# tophat.net
KiCad netlist of a schematic drawn in EAGLE
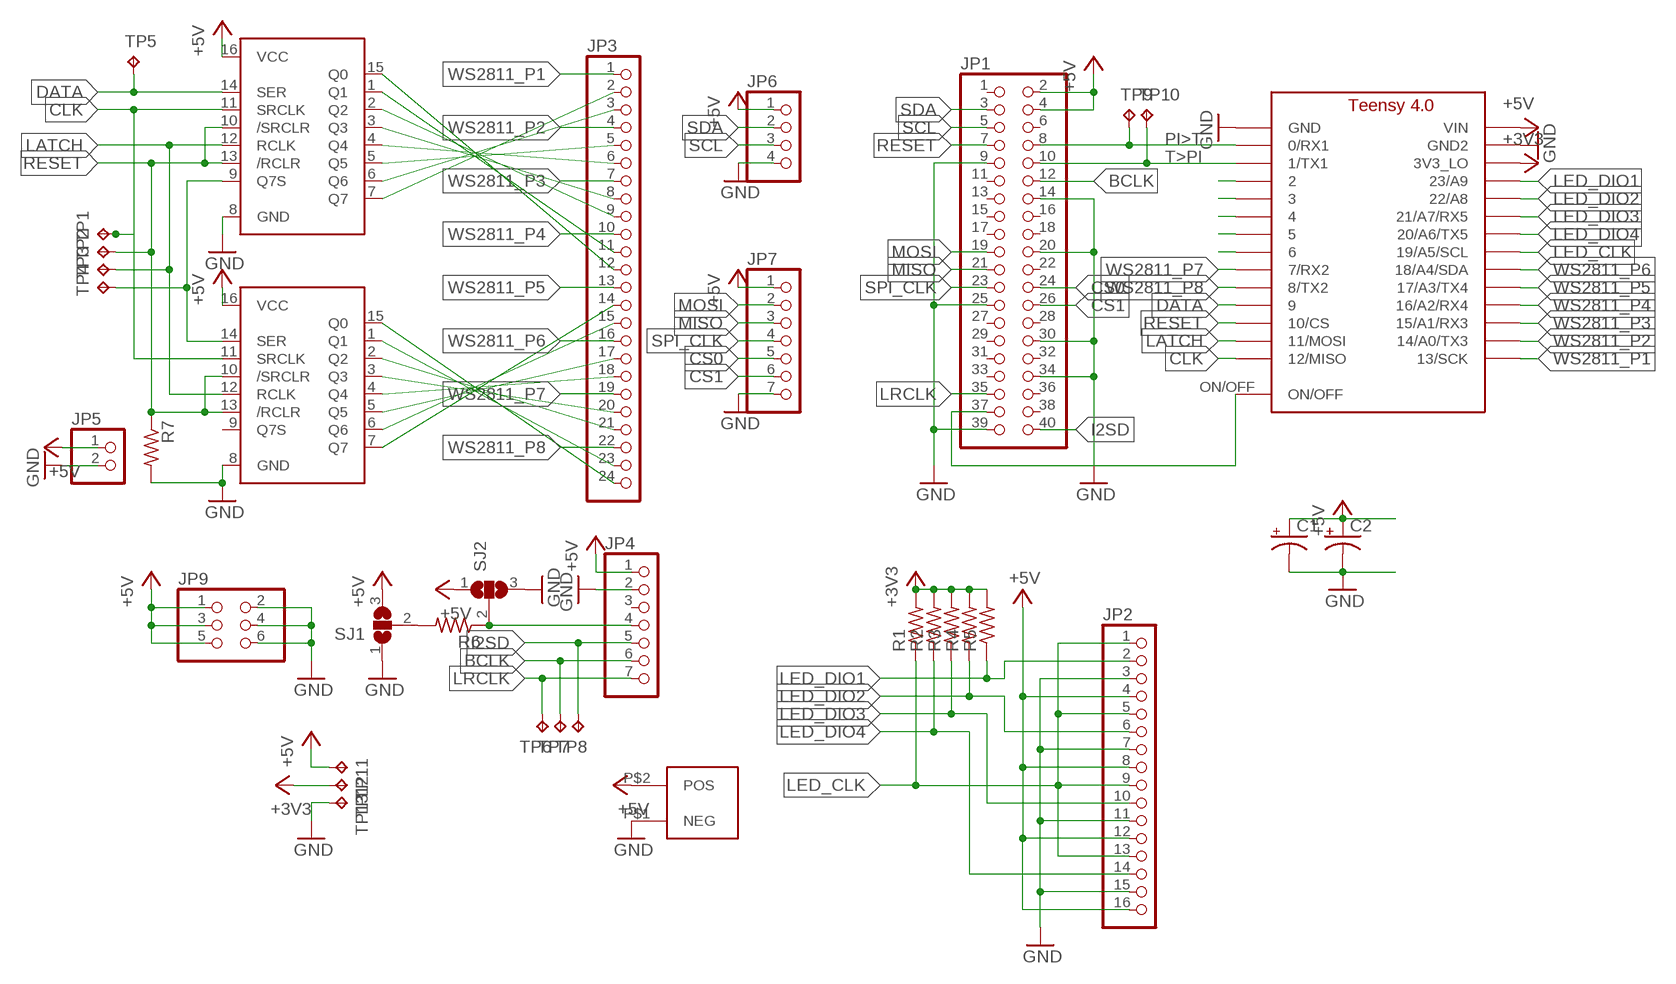
[diagram p0: schematic, sheet 1]

(export (version "E")
  (design (tool "Eeschema 10.0.6"))
  (components
    (comp (ref "C1")
      (value "CPOL-USE5-10.5")
      (footprint "eagle-import:E5-10,5")
      (libsource (lib "eagle-import") (part "CPOL-USE5-10.5"))
    )
    (comp (ref "C2")
      (value "CPOL-USE5-10.5")
      (footprint "eagle-import:E5-10,5")
      (libsource (lib "eagle-import") (part "CPOL-USE5-10.5"))
    )
    (comp (ref "JP1")
      (value "PINHD-2X20")
      (footprint "eagle-import:2X20")
      (libsource (lib "eagle-import") (part "PINHD-2X20"))
    )
    (comp (ref "JP2")
      (value "PINHD-1X16/90")
      (footprint "eagle-import:1X16_90")
      (libsource (lib "eagle-import") (part "PINHD-1X16/90"))
    )
    (comp (ref "JP3")
      (value "PINHD-1X24/90")
      (footprint "eagle-import:1X24_90")
      (libsource (lib "eagle-import") (part "PINHD-1X24/90"))
    )
    (comp (ref "JP4")
      (value "PINHD-1X7")
      (footprint "eagle-import:1X07")
      (libsource (lib "eagle-import") (part "PINHD-1X7"))
    )
    (comp (ref "JP5")
      (value "PINHD-1X2")
      (footprint "eagle-import:1X02")
      (libsource (lib "eagle-import") (part "PINHD-1X2"))
    )
    (comp (ref "JP6")
      (value "PINHD-1X4")
      (footprint "eagle-import:1X04")
      (libsource (lib "eagle-import") (part "PINHD-1X4"))
    )
    (comp (ref "JP7")
      (value "PINHD-1X7")
      (footprint "eagle-import:1X07")
      (libsource (lib "eagle-import") (part "PINHD-1X7"))
    )
    (comp (ref "JP8")
      (value "PWR_CONN")
      (footprint "eagle-import:PWR_CONN")
      (libsource (lib "eagle-import") (part "PWR_CONN"))
    )
    (comp (ref "JP9")
      (value "PINHD-2X3")
      (footprint "eagle-import:2X03")
      (libsource (lib "eagle-import") (part "PINHD-2X3"))
    )
    (comp (ref "R1")
      (value "R-US_0207/10")
      (footprint "eagle-import:0207_10")
      (libsource (lib "eagle-import") (part "R-US_0207/10"))
    )
    (comp (ref "R2")
      (value "R-US_0207/10")
      (footprint "eagle-import:0207_10")
      (libsource (lib "eagle-import") (part "R-US_0207/10"))
    )
    (comp (ref "R3")
      (value "R-US_0207/10")
      (footprint "eagle-import:0207_10")
      (libsource (lib "eagle-import") (part "R-US_0207/10"))
    )
    (comp (ref "R4")
      (value "R-US_0207/10")
      (footprint "eagle-import:0207_10")
      (libsource (lib "eagle-import") (part "R-US_0207/10"))
    )
    (comp (ref "R5")
      (value "R-US_0207/10")
      (footprint "eagle-import:0207_10")
      (libsource (lib "eagle-import") (part "R-US_0207/10"))
    )
    (comp (ref "R6")
      (value "R-US_0207/10")
      (footprint "eagle-import:0207_10")
      (libsource (lib "eagle-import") (part "R-US_0207/10"))
    )
    (comp (ref "R7")
      (value "R-US_0207/10")
      (footprint "eagle-import:0207_10")
      (libsource (lib "eagle-import") (part "R-US_0207/10"))
    )
    (comp (ref "SJ1")
      (value "SJ2W")
      (footprint "eagle-import:SJ_2")
      (libsource (lib "eagle-import") (part "SJ2W"))
    )
    (comp (ref "SJ2")
      (value "SJ2W")
      (footprint "eagle-import:SJ_2")
      (libsource (lib "eagle-import") (part "SJ2W"))
    )
    (comp (ref "TP1")
      (value "TPB2,54")
      (footprint "eagle-import:B2,54")
      (libsource (lib "eagle-import") (part "TPB2,54"))
    )
    (comp (ref "TP2")
      (value "TPB2,54")
      (footprint "eagle-import:B2,54")
      (libsource (lib "eagle-import") (part "TPB2,54"))
    )
    (comp (ref "TP3")
      (value "TPB2,54")
      (footprint "eagle-import:B2,54")
      (libsource (lib "eagle-import") (part "TPB2,54"))
    )
    (comp (ref "TP4")
      (value "TPB2,54")
      (footprint "eagle-import:B2,54")
      (libsource (lib "eagle-import") (part "TPB2,54"))
    )
    (comp (ref "TP5")
      (value "TPB2,54")
      (footprint "eagle-import:B2,54")
      (libsource (lib "eagle-import") (part "TPB2,54"))
    )
    (comp (ref "TP6")
      (value "TPB2,54")
      (footprint "eagle-import:B2,54")
      (libsource (lib "eagle-import") (part "TPB2,54"))
    )
    (comp (ref "TP7")
      (value "TPB2,54")
      (footprint "eagle-import:B2,54")
      (libsource (lib "eagle-import") (part "TPB2,54"))
    )
    (comp (ref "TP8")
      (value "TPB2,54")
      (footprint "eagle-import:B2,54")
      (libsource (lib "eagle-import") (part "TPB2,54"))
    )
    (comp (ref "TP9")
      (value "TPB2,54")
      (footprint "eagle-import:B2,54")
      (libsource (lib "eagle-import") (part "TPB2,54"))
    )
    (comp (ref "TP10")
      (value "TPB2,54")
      (footprint "eagle-import:B2,54")
      (libsource (lib "eagle-import") (part "TPB2,54"))
    )
    (comp (ref "TP11")
      (value "TPB2,54")
      (footprint "eagle-import:B2,54")
      (libsource (lib "eagle-import") (part "TPB2,54"))
    )
    (comp (ref "TP12")
      (value "TPB2,54")
      (footprint "eagle-import:B2,54")
      (libsource (lib "eagle-import") (part "TPB2,54"))
    )
    (comp (ref "TP13")
      (value "TPB2,54")
      (footprint "eagle-import:B2,54")
      (libsource (lib "eagle-import") (part "TPB2,54"))
    )
    (comp (ref "U$1")
      (value "TEENSY_4.0")
      (footprint "eagle-import:TEENSY_4.0")
      (libsource (lib "eagle-import") (part "TEENSY_4.0"))
    )
    (comp (ref "U$2")
      (value "74AHCT95")
      (footprint "eagle-import:SOIC127P600X175-16N")
      (libsource (lib "eagle-import") (part "74AHCT95"))
    )
    (comp (ref "U$3")
      (value "74AHCT95")
      (footprint "eagle-import:SOIC127P600X175-16N")
      (libsource (lib "eagle-import") (part "74AHCT95"))
    )
  )
  (nets
    (net (code "1") (name "+3V3") (class "Default")
      (node (ref "R1") (pin "2") (pinfunction "2_2") (pintype "passive"))
      (node (ref "R2") (pin "2") (pinfunction "2_2") (pintype "passive"))
      (node (ref "R3") (pin "2") (pinfunction "2_2") (pintype "passive"))
      (node (ref "R4") (pin "2") (pinfunction "2_2") (pintype "passive"))
      (node (ref "R5") (pin "2") (pinfunction "2_2") (pintype "passive"))
      (node (ref "TP12") (pin "TP") (pinfunction "TP_TP") (pintype "input"))
      (node (ref "U$1") (pin "3V3_LO") (pinfunction "3V3_LO_3V3_LO") (pintype "bidirectional"))
    )
    (net (code "2") (name "+5V") (class "Default")
      (node (ref "C1") (pin "+") (pinfunction "+_+") (pintype "passive"))
      (node (ref "C2") (pin "+") (pinfunction "+_+") (pintype "passive"))
      (node (ref "JP1") (pin "2") (pinfunction "2_2") (pintype "passive"))
      (node (ref "JP1") (pin "4") (pinfunction "4_4") (pintype "passive"))
      (node (ref "JP2") (pin "12") (pinfunction "12_12") (pintype "passive"))
      (node (ref "JP2") (pin "16") (pinfunction "16_16") (pintype "passive"))
      (node (ref "JP2") (pin "4") (pinfunction "4_4") (pintype "passive"))
      (node (ref "JP2") (pin "8") (pinfunction "8_8") (pintype "passive"))
      (node (ref "JP4") (pin "1") (pinfunction "1_1") (pintype "passive"))
      (node (ref "JP5") (pin "1") (pinfunction "1_1") (pintype "passive"))
      (node (ref "JP6") (pin "1") (pinfunction "1_1") (pintype "passive"))
      (node (ref "JP7") (pin "1") (pinfunction "1_1") (pintype "passive"))
      (node (ref "JP8") (pin "P$2") (pinfunction "POS_P$2") (pintype "bidirectional"))
      (node (ref "JP9") (pin "1") (pinfunction "1_1") (pintype "passive"))
      (node (ref "JP9") (pin "3") (pinfunction "3_3") (pintype "passive"))
      (node (ref "JP9") (pin "5") (pinfunction "5_5") (pintype "passive"))
      (node (ref "SJ1") (pin "3") (pinfunction "3_3") (pintype "passive"))
      (node (ref "SJ2") (pin "1") (pinfunction "1_1") (pintype "passive"))
      (node (ref "TP11") (pin "TP") (pinfunction "TP_TP") (pintype "input"))
      (node (ref "U$1") (pin "VIN") (pinfunction "VIN_VIN") (pintype "bidirectional"))
      (node (ref "U$2") (pin "16") (pinfunction "VCC_16") (pintype "bidirectional"))
      (node (ref "U$3") (pin "16") (pinfunction "VCC_16") (pintype "bidirectional"))
    )
    (net (code "3") (name "/PI>T") (class "Default")
      (node (ref "JP1") (pin "8") (pinfunction "8_8") (pintype "passive"))
      (node (ref "TP9") (pin "TP") (pinfunction "TP_TP") (pintype "input"))
      (node (ref "U$1") (pin "0/RX") (pinfunction "0/RX1_0/RX") (pintype "bidirectional"))
    )
    (net (code "4") (name "/T>PI") (class "Default")
      (node (ref "JP1") (pin "10") (pinfunction "10_10") (pintype "passive"))
      (node (ref "TP10") (pin "TP") (pinfunction "TP_TP") (pintype "input"))
      (node (ref "U$1") (pin "1/TX") (pinfunction "1/TX1_1/TX") (pintype "bidirectional"))
    )
    (net (code "5") (name "BCLK") (class "Default")
      (node (ref "JP1") (pin "12") (pinfunction "12_12") (pintype "passive"))
      (node (ref "JP4") (pin "6") (pinfunction "6_6") (pintype "passive"))
      (node (ref "TP7") (pin "TP") (pinfunction "TP_TP") (pintype "input"))
    )
    (net (code "6") (name "CLK") (class "Default")
      (node (ref "TP1") (pin "TP") (pinfunction "TP_TP") (pintype "input"))
      (node (ref "U$1") (pin "12/MISO") (pinfunction "12/MISO_12/MISO") (pintype "bidirectional"))
      (node (ref "U$2") (pin "11") (pinfunction "SRCLK_11") (pintype "bidirectional"))
      (node (ref "U$3") (pin "11") (pinfunction "SRCLK_11") (pintype "bidirectional"))
    )
    (net (code "7") (name "CS0") (class "Default")
      (node (ref "JP1") (pin "24") (pinfunction "24_24") (pintype "passive"))
      (node (ref "JP7") (pin "5") (pinfunction "5_5") (pintype "passive"))
    )
    (net (code "8") (name "CS1") (class "Default")
      (node (ref "JP1") (pin "26") (pinfunction "26_26") (pintype "passive"))
      (node (ref "JP7") (pin "6") (pinfunction "6_6") (pintype "passive"))
    )
    (net (code "9") (name "DATA") (class "Default")
      (node (ref "TP5") (pin "TP") (pinfunction "TP_TP") (pintype "input"))
      (node (ref "U$1") (pin "9/CS") (pinfunction "9_9/CS") (pintype "bidirectional"))
      (node (ref "U$2") (pin "14") (pinfunction "SER_14") (pintype "bidirectional"))
    )
    (net (code "10") (name "GND") (class "Default")
      (node (ref "C1") (pin "-") (pinfunction "-_-") (pintype "passive"))
      (node (ref "C2") (pin "-") (pinfunction "-_-") (pintype "passive"))
      (node (ref "JP1") (pin "14") (pinfunction "14_14") (pintype "passive"))
      (node (ref "JP1") (pin "20") (pinfunction "20_20") (pintype "passive"))
      (node (ref "JP1") (pin "25") (pinfunction "25_25") (pintype "passive"))
      (node (ref "JP1") (pin "30") (pinfunction "30_30") (pintype "passive"))
      (node (ref "JP1") (pin "34") (pinfunction "34_34") (pintype "passive"))
      (node (ref "JP1") (pin "39") (pinfunction "39_39") (pintype "passive"))
      (node (ref "JP1") (pin "9") (pinfunction "9_9") (pintype "passive"))
      (node (ref "JP2") (pin "11") (pinfunction "11_11") (pintype "passive"))
      (node (ref "JP2") (pin "15") (pinfunction "15_15") (pintype "passive"))
      (node (ref "JP2") (pin "3") (pinfunction "3_3") (pintype "passive"))
      (node (ref "JP2") (pin "7") (pinfunction "7_7") (pintype "passive"))
      (node (ref "JP4") (pin "2") (pinfunction "2_2") (pintype "passive"))
      (node (ref "JP5") (pin "2") (pinfunction "2_2") (pintype "passive"))
      (node (ref "JP6") (pin "4") (pinfunction "4_4") (pintype "passive"))
      (node (ref "JP7") (pin "7") (pinfunction "7_7") (pintype "passive"))
      (node (ref "JP8") (pin "P$1") (pinfunction "NEG_P$1") (pintype "bidirectional"))
      (node (ref "JP9") (pin "2") (pinfunction "2_2") (pintype "passive"))
      (node (ref "JP9") (pin "4") (pinfunction "4_4") (pintype "passive"))
      (node (ref "JP9") (pin "6") (pinfunction "6_6") (pintype "passive"))
      (node (ref "R7") (pin "2") (pinfunction "2_2") (pintype "passive"))
      (node (ref "SJ1") (pin "1") (pinfunction "1_1") (pintype "passive"))
      (node (ref "SJ2") (pin "3") (pinfunction "3_3") (pintype "passive"))
      (node (ref "TP13") (pin "TP") (pinfunction "TP_TP") (pintype "input"))
      (node (ref "U$1") (pin "GND") (pinfunction "GND_GND") (pintype "bidirectional"))
      (node (ref "U$1") (pin "GND2") (pinfunction "GND2_GND2") (pintype "bidirectional"))
      (node (ref "U$2") (pin "8") (pinfunction "GND_8") (pintype "bidirectional"))
      (node (ref "U$3") (pin "8") (pinfunction "GND_8") (pintype "bidirectional"))
    )
    (net (code "11") (name "I2SD") (class "Default")
      (node (ref "JP1") (pin "40") (pinfunction "40_40") (pintype "passive"))
      (node (ref "JP4") (pin "5") (pinfunction "5_5") (pintype "passive"))
      (node (ref "TP8") (pin "TP") (pinfunction "TP_TP") (pintype "input"))
    )
    (net (code "12") (name "LATCH") (class "Default")
      (node (ref "TP3") (pin "TP") (pinfunction "TP_TP") (pintype "input"))
      (node (ref "U$1") (pin "11/MOSI") (pinfunction "11/MOSI_11/MOSI") (pintype "bidirectional"))
      (node (ref "U$2") (pin "12") (pinfunction "RCLK_12") (pintype "bidirectional"))
      (node (ref "U$3") (pin "12") (pinfunction "RCLK_12") (pintype "bidirectional"))
    )
    (net (code "13") (name "LED_CLK") (class "Default")
      (node (ref "JP2") (pin "1") (pinfunction "1_1") (pintype "passive"))
      (node (ref "JP2") (pin "13") (pinfunction "13_13") (pintype "passive"))
      (node (ref "JP2") (pin "5") (pinfunction "5_5") (pintype "passive"))
      (node (ref "JP2") (pin "9") (pinfunction "9_9") (pintype "passive"))
      (node (ref "R1") (pin "1") (pinfunction "1_1") (pintype "passive"))
      (node (ref "U$1") (pin "19/A5/SCL") (pinfunction "19/A5/SCL_19/A5/SCL") (pintype "bidirectional"))
    )
    (net (code "14") (name "LED_DIO1") (class "Default")
      (node (ref "JP2") (pin "2") (pinfunction "2_2") (pintype "passive"))
      (node (ref "R5") (pin "1") (pinfunction "1_1") (pintype "passive"))
      (node (ref "U$1") (pin "23/A9") (pinfunction "23/A9_23/A9") (pintype "bidirectional"))
    )
    (net (code "15") (name "LED_DIO2") (class "Default")
      (node (ref "JP2") (pin "6") (pinfunction "6_6") (pintype "passive"))
      (node (ref "R4") (pin "1") (pinfunction "1_1") (pintype "passive"))
      (node (ref "U$1") (pin "22/A8") (pinfunction "22/A8_22/A8") (pintype "bidirectional"))
    )
    (net (code "16") (name "LED_DIO3") (class "Default")
      (node (ref "JP2") (pin "10") (pinfunction "10_10") (pintype "passive"))
      (node (ref "R3") (pin "1") (pinfunction "1_1") (pintype "passive"))
      (node (ref "U$1") (pin "21/A7") (pinfunction "21/A7/RX5_21/A7") (pintype "bidirectional"))
    )
    (net (code "17") (name "LED_DIO4") (class "Default")
      (node (ref "JP2") (pin "14") (pinfunction "14_14") (pintype "passive"))
      (node (ref "R2") (pin "1") (pinfunction "1_1") (pintype "passive"))
      (node (ref "U$1") (pin "20/A6") (pinfunction "20/A6/TX5_20/A6") (pintype "bidirectional"))
    )
    (net (code "18") (name "LRCLK") (class "Default")
      (node (ref "JP1") (pin "35") (pinfunction "35_35") (pintype "passive"))
      (node (ref "JP4") (pin "7") (pinfunction "7_7") (pintype "passive"))
      (node (ref "TP6") (pin "TP") (pinfunction "TP_TP") (pintype "input"))
    )
    (net (code "19") (name "MISO") (class "Default")
      (node (ref "JP1") (pin "21") (pinfunction "21_21") (pintype "passive"))
      (node (ref "JP7") (pin "3") (pinfunction "3_3") (pintype "passive"))
    )
    (net (code "20") (name "MOSI") (class "Default")
      (node (ref "JP1") (pin "19") (pinfunction "19_19") (pintype "passive"))
      (node (ref "JP7") (pin "2") (pinfunction "2_2") (pintype "passive"))
    )
    (net (code "21") (name "Net-(JP1-Pad37)") (class "Default")
      (node (ref "JP1") (pin "37") (pinfunction "37_37") (pintype "passive"))
      (node (ref "U$1") (pin "ON/OFF") (pinfunction "ON/OFF_ON/OFF") (pintype "bidirectional"))
    )
    (net (code "22") (name "Net-(JP4-Pad4)") (class "Default")
      (node (ref "JP4") (pin "4") (pinfunction "4_4") (pintype "passive"))
      (node (ref "R6") (pin "1") (pinfunction "1_1") (pintype "passive"))
      (node (ref "SJ2") (pin "2") (pinfunction "2_2") (pintype "passive"))
    )
    (net (code "23") (name "Net-(R6-Pad2)") (class "Default")
      (node (ref "R6") (pin "2") (pinfunction "2_2") (pintype "passive"))
      (node (ref "SJ1") (pin "2") (pinfunction "2_2") (pintype "passive"))
    )
    (net (code "24") (name "Net-(U$2-Q0)") (class "Default")
      (node (ref "JP3") (pin "12") (pinfunction "12_12") (pintype "passive"))
      (node (ref "U$2") (pin "15") (pinfunction "Q0_15") (pintype "bidirectional"))
    )
    (net (code "25") (name "Net-(U$2-Q1)") (class "Default")
      (node (ref "JP3") (pin "11") (pinfunction "11_11") (pintype "passive"))
      (node (ref "U$2") (pin "1") (pinfunction "Q1_1") (pintype "bidirectional"))
    )
    (net (code "26") (name "Net-(U$2-Q2)") (class "Default")
      (node (ref "JP3") (pin "9") (pinfunction "9_9") (pintype "passive"))
      (node (ref "U$2") (pin "2") (pinfunction "Q2_2") (pintype "bidirectional"))
    )
    (net (code "27") (name "Net-(U$2-Q3)") (class "Default")
      (node (ref "JP3") (pin "8") (pinfunction "8_8") (pintype "passive"))
      (node (ref "U$2") (pin "3") (pinfunction "Q3_3") (pintype "bidirectional"))
    )
    (net (code "28") (name "Net-(U$2-Q4)") (class "Default")
      (node (ref "JP3") (pin "6") (pinfunction "6_6") (pintype "passive"))
      (node (ref "U$2") (pin "4") (pinfunction "Q4_4") (pintype "bidirectional"))
    )
    (net (code "29") (name "Net-(U$2-Q5)") (class "Default")
      (node (ref "JP3") (pin "5") (pinfunction "5_5") (pintype "passive"))
      (node (ref "U$2") (pin "5") (pinfunction "Q5_5") (pintype "bidirectional"))
    )
    (net (code "30") (name "Net-(U$2-Q6)") (class "Default")
      (node (ref "JP3") (pin "3") (pinfunction "3_3") (pintype "passive"))
      (node (ref "U$2") (pin "6") (pinfunction "Q6_6") (pintype "bidirectional"))
    )
    (net (code "31") (name "Net-(U$2-Q7)") (class "Default")
      (node (ref "JP3") (pin "2") (pinfunction "2_2") (pintype "passive"))
      (node (ref "U$2") (pin "7") (pinfunction "Q7_7") (pintype "bidirectional"))
    )
    (net (code "32") (name "Net-(U$2-Q7S)") (class "Default")
      (node (ref "TP4") (pin "TP") (pinfunction "TP_TP") (pintype "input"))
      (node (ref "U$2") (pin "9") (pinfunction "Q7S_9") (pintype "bidirectional"))
      (node (ref "U$3") (pin "14") (pinfunction "SER_14") (pintype "bidirectional"))
    )
    (net (code "33") (name "Net-(U$3-Q0)") (class "Default")
      (node (ref "JP3") (pin "24") (pinfunction "24_24") (pintype "passive"))
      (node (ref "U$3") (pin "15") (pinfunction "Q0_15") (pintype "bidirectional"))
    )
    (net (code "34") (name "Net-(U$3-Q1)") (class "Default")
      (node (ref "JP3") (pin "23") (pinfunction "23_23") (pintype "passive"))
      (node (ref "U$3") (pin "1") (pinfunction "Q1_1") (pintype "bidirectional"))
    )
    (net (code "35") (name "Net-(U$3-Q2)") (class "Default")
      (node (ref "JP3") (pin "21") (pinfunction "21_21") (pintype "passive"))
      (node (ref "U$3") (pin "2") (pinfunction "Q2_2") (pintype "bidirectional"))
    )
    (net (code "36") (name "Net-(U$3-Q3)") (class "Default")
      (node (ref "JP3") (pin "20") (pinfunction "20_20") (pintype "passive"))
      (node (ref "U$3") (pin "3") (pinfunction "Q3_3") (pintype "bidirectional"))
    )
    (net (code "37") (name "Net-(U$3-Q4)") (class "Default")
      (node (ref "JP3") (pin "18") (pinfunction "18_18") (pintype "passive"))
      (node (ref "U$3") (pin "4") (pinfunction "Q4_4") (pintype "bidirectional"))
    )
    (net (code "38") (name "Net-(U$3-Q5)") (class "Default")
      (node (ref "JP3") (pin "17") (pinfunction "17_17") (pintype "passive"))
      (node (ref "U$3") (pin "5") (pinfunction "Q5_5") (pintype "bidirectional"))
    )
    (net (code "39") (name "Net-(U$3-Q6)") (class "Default")
      (node (ref "JP3") (pin "15") (pinfunction "15_15") (pintype "passive"))
      (node (ref "U$3") (pin "6") (pinfunction "Q6_6") (pintype "bidirectional"))
    )
    (net (code "40") (name "Net-(U$3-Q7)") (class "Default")
      (node (ref "JP3") (pin "14") (pinfunction "14_14") (pintype "passive"))
      (node (ref "U$3") (pin "7") (pinfunction "Q7_7") (pintype "bidirectional"))
    )
    (net (code "41") (name "RESET") (class "Default")
      (node (ref "JP1") (pin "7") (pinfunction "7_7") (pintype "passive"))
      (node (ref "R7") (pin "1") (pinfunction "1_1") (pintype "passive"))
      (node (ref "TP2") (pin "TP") (pinfunction "TP_TP") (pintype "input"))
      (node (ref "U$1") (pin "10/CS") (pinfunction "10/CS_10/CS") (pintype "bidirectional"))
      (node (ref "U$2") (pin "10") (pinfunction "/SRCLR_10") (pintype "bidirectional"))
      (node (ref "U$2") (pin "13") (pinfunction "/RCLR_13") (pintype "bidirectional"))
      (node (ref "U$3") (pin "10") (pinfunction "/SRCLR_10") (pintype "bidirectional"))
      (node (ref "U$3") (pin "13") (pinfunction "/RCLR_13") (pintype "bidirectional"))
    )
    (net (code "42") (name "SCL") (class "Default")
      (node (ref "JP1") (pin "5") (pinfunction "5_5") (pintype "passive"))
      (node (ref "JP6") (pin "3") (pinfunction "3_3") (pintype "passive"))
    )
    (net (code "43") (name "SDA") (class "Default")
      (node (ref "JP1") (pin "3") (pinfunction "3_3") (pintype "passive"))
      (node (ref "JP6") (pin "2") (pinfunction "2_2") (pintype "passive"))
    )
    (net (code "44") (name "SPI_CLK") (class "Default")
      (node (ref "JP1") (pin "23") (pinfunction "23_23") (pintype "passive"))
      (node (ref "JP7") (pin "4") (pinfunction "4_4") (pintype "passive"))
    )
    (net (code "45") (name "WS2811_P1") (class "Default")
      (node (ref "JP3") (pin "1") (pinfunction "1_1") (pintype "passive"))
      (node (ref "U$1") (pin "13/SCK") (pinfunction "13/SCK_13/SCK") (pintype "bidirectional"))
    )
    (net (code "46") (name "WS2811_P2") (class "Default")
      (node (ref "JP3") (pin "4") (pinfunction "4_4") (pintype "passive"))
      (node (ref "U$1") (pin "14/A0") (pinfunction "14/A0/TX3_14/A0") (pintype "bidirectional"))
    )
    (net (code "47") (name "WS2811_P3") (class "Default")
      (node (ref "JP3") (pin "7") (pinfunction "7_7") (pintype "passive"))
      (node (ref "U$1") (pin "15/A1") (pinfunction "15/A1/RX3_15/A1") (pintype "bidirectional"))
    )
    (net (code "48") (name "WS2811_P4") (class "Default")
      (node (ref "JP3") (pin "10") (pinfunction "10_10") (pintype "passive"))
      (node (ref "U$1") (pin "16/A2") (pinfunction "16/A2/RX4_16/A2") (pintype "bidirectional"))
    )
    (net (code "49") (name "WS2811_P5") (class "Default")
      (node (ref "JP3") (pin "13") (pinfunction "13_13") (pintype "passive"))
      (node (ref "U$1") (pin "17/A3") (pinfunction "17/A3/TX4_17/A3") (pintype "bidirectional"))
    )
    (net (code "50") (name "WS2811_P6") (class "Default")
      (node (ref "JP3") (pin "16") (pinfunction "16_16") (pintype "passive"))
      (node (ref "U$1") (pin "18/A4/SDA") (pinfunction "18/A4/SDA_18/A4/SDA") (pintype "bidirectional"))
    )
    (net (code "51") (name "WS2811_P7") (class "Default")
      (node (ref "JP3") (pin "19") (pinfunction "19_19") (pintype "passive"))
      (node (ref "U$1") (pin "7") (pinfunction "7/RX2_7") (pintype "bidirectional"))
    )
    (net (code "52") (name "WS2811_P8") (class "Default")
      (node (ref "JP3") (pin "22") (pinfunction "22_22") (pintype "passive"))
      (node (ref "U$1") (pin "8") (pinfunction "8/TX2_8") (pintype "bidirectional"))
    )
    (net (code "53") (name "unconnected-(JP1-Pad1)") (class "Default")
      (node (ref "JP1") (pin "1") (pinfunction "1_1") (pintype "passive"))
    )
    (net (code "54") (name "unconnected-(JP1-Pad6)") (class "Default")
      (node (ref "JP1") (pin "6") (pinfunction "6_6") (pintype "passive"))
    )
    (net (code "55") (name "unconnected-(JP1-Pad11)") (class "Default")
      (node (ref "JP1") (pin "11") (pinfunction "11_11") (pintype "passive"))
    )
    (net (code "56") (name "unconnected-(JP1-Pad13)") (class "Default")
      (node (ref "JP1") (pin "13") (pinfunction "13_13") (pintype "passive"))
    )
    (net (code "57") (name "unconnected-(JP1-Pad15)") (class "Default")
      (node (ref "JP1") (pin "15") (pinfunction "15_15") (pintype "passive"))
    )
    (net (code "58") (name "unconnected-(JP1-Pad16)") (class "Default")
      (node (ref "JP1") (pin "16") (pinfunction "16_16") (pintype "passive"))
    )
    (net (code "59") (name "unconnected-(JP1-Pad17)") (class "Default")
      (node (ref "JP1") (pin "17") (pinfunction "17_17") (pintype "passive"))
    )
    (net (code "60") (name "unconnected-(JP1-Pad18)") (class "Default")
      (node (ref "JP1") (pin "18") (pinfunction "18_18") (pintype "passive"))
    )
    (net (code "61") (name "unconnected-(JP1-Pad22)") (class "Default")
      (node (ref "JP1") (pin "22") (pinfunction "22_22") (pintype "passive"))
    )
    (net (code "62") (name "unconnected-(JP1-Pad27)") (class "Default")
      (node (ref "JP1") (pin "27") (pinfunction "27_27") (pintype "passive"))
    )
    (net (code "63") (name "unconnected-(JP1-Pad28)") (class "Default")
      (node (ref "JP1") (pin "28") (pinfunction "28_28") (pintype "passive"))
    )
    (net (code "64") (name "unconnected-(JP1-Pad29)") (class "Default")
      (node (ref "JP1") (pin "29") (pinfunction "29_29") (pintype "passive"))
    )
    (net (code "65") (name "unconnected-(JP1-Pad31)") (class "Default")
      (node (ref "JP1") (pin "31") (pinfunction "31_31") (pintype "passive"))
    )
    (net (code "66") (name "unconnected-(JP1-Pad32)") (class "Default")
      (node (ref "JP1") (pin "32") (pinfunction "32_32") (pintype "passive"))
    )
    (net (code "67") (name "unconnected-(JP1-Pad33)") (class "Default")
      (node (ref "JP1") (pin "33") (pinfunction "33_33") (pintype "passive"))
    )
    (net (code "68") (name "unconnected-(JP1-Pad36)") (class "Default")
      (node (ref "JP1") (pin "36") (pinfunction "36_36") (pintype "passive"))
    )
    (net (code "69") (name "unconnected-(JP1-Pad38)") (class "Default")
      (node (ref "JP1") (pin "38") (pinfunction "38_38") (pintype "passive"))
    )
    (net (code "70") (name "unconnected-(JP4-Pad3)") (class "Default")
      (node (ref "JP4") (pin "3") (pinfunction "3_3") (pintype "passive"))
    )
    (net (code "71") (name "unconnected-(U$1-3-Pad3{slash}CANTX)") (class "Default")
      (node (ref "U$1") (pin "3/CANTX") (pinfunction "3_3/CANTX") (pintype "bidirectional"))
    )
    (net (code "72") (name "unconnected-(U$1-4-Pad4{slash}CANRX)") (class "Default")
      (node (ref "U$1") (pin "4/CANRX") (pinfunction "4_4/CANRX") (pintype "bidirectional"))
    )
    (net (code "73") (name "unconnected-(U$1-Pad2)") (class "Default")
      (node (ref "U$1") (pin "2") (pinfunction "2_2") (pintype "bidirectional"))
    )
    (net (code "74") (name "unconnected-(U$1-Pad5)") (class "Default")
      (node (ref "U$1") (pin "5") (pinfunction "5_5") (pintype "bidirectional"))
    )
    (net (code "75") (name "unconnected-(U$1-Pad6)") (class "Default")
      (node (ref "U$1") (pin "6") (pinfunction "6_6") (pintype "bidirectional"))
    )
    (net (code "76") (name "unconnected-(U$3-Q7S-Pad9)") (class "Default")
      (node (ref "U$3") (pin "9") (pinfunction "Q7S_9") (pintype "bidirectional"))
    )
  )
)
